# 4_RK3399_EMMC_ADC_PCIE.net
KiCad netlist of a schematic drawn in Altium Designer
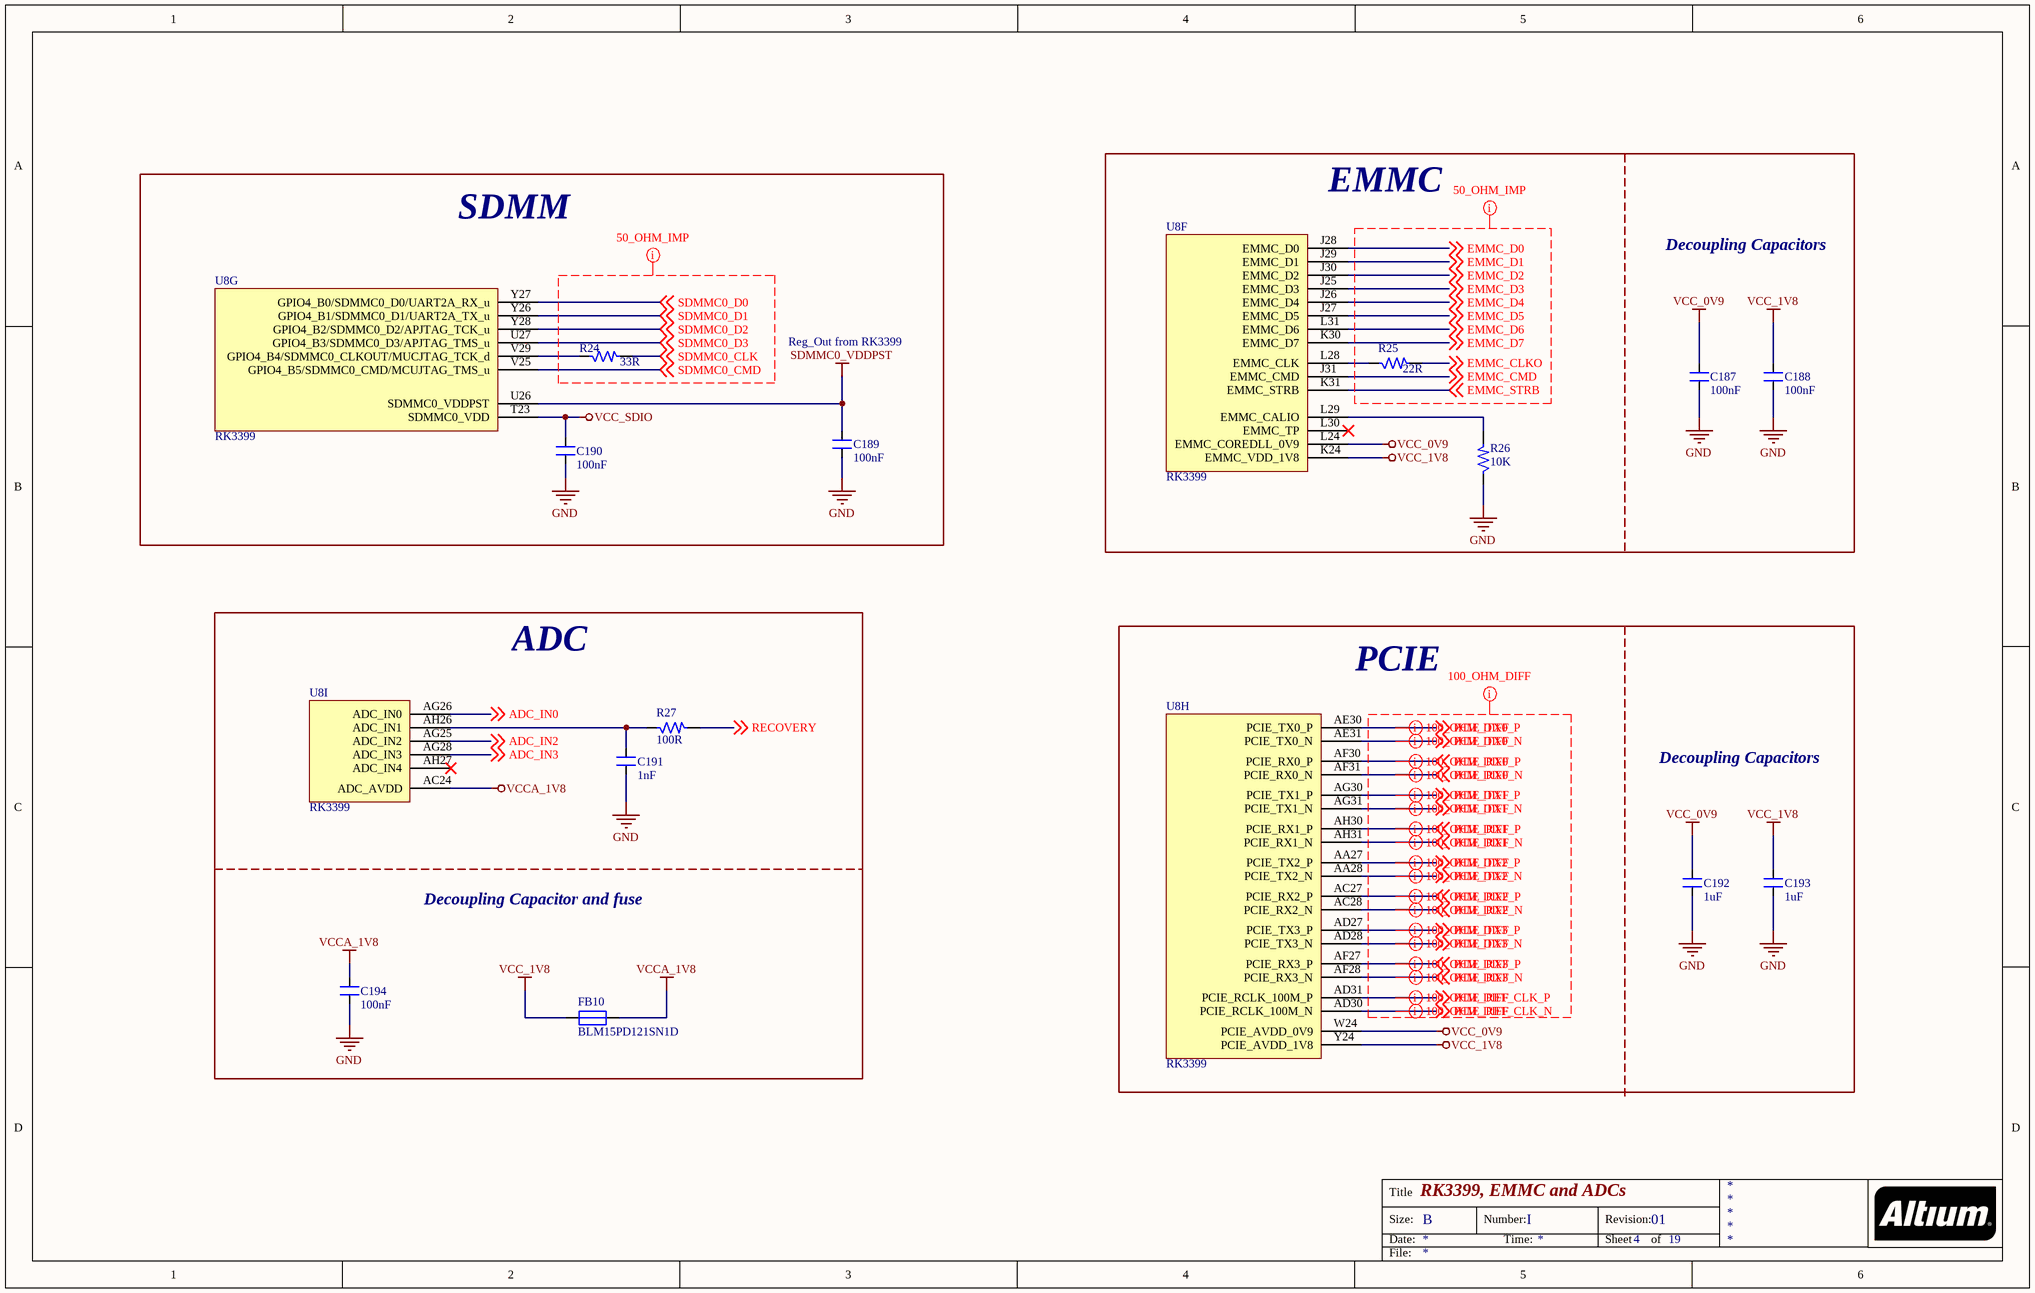
[diagram p0: [4] RK3399_EMMC_ADC_PCIE.SchDoc]

(export (version "E")
  (design (tool "Eeschema 10.0.6"))
  (components
    (comp (ref "C187")
      (value "100nF")
      (footprint "CAP_0201")
      (description "0.1µF ±10% 25V Ceramic Capacitor X5R 0201 (0603 Metric)")
      (fields
        (field (name "MANUFACTURER") "TDK Corporation")
        (field (name "MANUFACTURER PART NUMBER") "C0603X5R1E104K030BB")
      )
      (libsource (lib "EsteemPCB_SOM_Course_intlib") (part "CAP_100nF-25V-10%-0201"))
    )
    (comp (ref "C188")
      (value "100nF")
      (footprint "CAP_0201")
      (description "0.1µF ±10% 25V Ceramic Capacitor X5R 0201 (0603 Metric)")
      (fields
        (field (name "MANUFACTURER") "TDK Corporation")
        (field (name "MANUFACTURER PART NUMBER") "C0603X5R1E104K030BB")
      )
      (libsource (lib "EsteemPCB_SOM_Course_intlib") (part "CAP_100nF-25V-10%-0201"))
    )
    (comp (ref "C189")
      (value "100nF")
      (footprint "CAP_0201")
      (description "0.1µF ±10% 25V Ceramic Capacitor X5R 0201 (0603 Metric)")
      (fields
        (field (name "MANUFACTURER") "TDK Corporation")
        (field (name "MANUFACTURER PART NUMBER") "C0603X5R1E104K030BB")
      )
      (libsource (lib "EsteemPCB_SOM_Course_intlib") (part "CAP_100nF-25V-10%-0201"))
    )
    (comp (ref "C190")
      (value "100nF")
      (footprint "CAP_0201")
      (description "0.1µF ±10% 25V Ceramic Capacitor X5R 0201 (0603 Metric)")
      (fields
        (field (name "MANUFACTURER") "TDK Corporation")
        (field (name "MANUFACTURER PART NUMBER") "C0603X5R1E104K030BB")
      )
      (libsource (lib "EsteemPCB_SOM_Course_intlib") (part "CAP_100nF-25V-10%-0201"))
    )
    (comp (ref "C191")
      (value "1nF")
      (footprint "CAP_0201")
      (description "1000pF ±10% 16V Ceramic Capacitor X7R 0201 (0603 Metric)")
      (fields
        (field (name "MANUFACTURER") "Murata Electronics")
        (field (name "MANUFACTURER PART NUMBER") "GRM033R71C102KA01D")
      )
      (libsource (lib "EsteemPCB_SOM_Course_intlib") (part "CAP_1nF-16V-10%-0201"))
    )
    (comp (ref "C192")
      (value "1uF")
      (footprint "CAP_0201")
      (description "1µF ±20% 16V Ceramic Capacitor X5R 0201 (0603 Metric)")
      (fields
        (field (name "MANUFACTURER") "Samsung Electro-Mechanics")
        (field (name "MANUFACTURER PART NUMBER") "CL03A105MO3NRNH")
      )
      (libsource (lib "EsteemPCB_SOM_Course_intlib") (part "CAP_1uF-16V-10%-0201"))
    )
    (comp (ref "C193")
      (value "1uF")
      (footprint "CAP_0201")
      (description "1µF ±20% 16V Ceramic Capacitor X5R 0201 (0603 Metric)")
      (fields
        (field (name "MANUFACTURER") "Samsung Electro-Mechanics")
        (field (name "MANUFACTURER PART NUMBER") "CL03A105MO3NRNH")
      )
      (libsource (lib "EsteemPCB_SOM_Course_intlib") (part "CAP_1uF-16V-10%-0201"))
    )
    (comp (ref "C194")
      (value "100nF")
      (footprint "CAP_0201")
      (description "0.1µF ±10% 25V Ceramic Capacitor X5R 0201 (0603 Metric)")
      (fields
        (field (name "MANUFACTURER") "TDK Corporation")
        (field (name "MANUFACTURER PART NUMBER") "C0603X5R1E104K030BB")
      )
      (libsource (lib "EsteemPCB_SOM_Course_intlib") (part "CAP_100nF-25V-10%-0201"))
    )
    (comp (ref "FB10")
      (value "BLM15PD121SN1D")
      (footprint "RES_0402")
      (description "120 Ohms @ 100MHz 1 Power Line Ferrite Bead 0402 (1005 Metric) 1.3A 90mOhm")
      (fields (field (name "MANUFACTURER") "Murata Electronics"))
      (libsource (lib "EsteemPCB_SOM_Course_intlib") (part "FB_120R-1.3A-100Mhz-0402"))
    )
    (comp (ref "R24")
      (value "33R")
      (footprint "RES_0201")
      (description "33 Ohms ±1% 0.05W, 1/20W Chip Resistor 0201 (0603 Metric) Thick Film")
      (fields
        (field (name "MANUFACTURER") "Yageo")
        (field (name "MANUFACTURER PART NUMBER") "RC0201FR-0733RL")
      )
      (libsource (lib "EsteemPCB_SOM_Course_intlib") (part "RES_33R-0.05W-1%-0201"))
    )
    (comp (ref "R25")
      (value "22R")
      (footprint "RES_0201")
      (description "22 Ohms ±1% 0.05W, 1/20W Chip Resistor 0201 (0603 Metric) Moisture Resistant Thick Film")
      (fields
        (field (name "MANUFACTURER") "Yageo")
        (field (name "MANUFACTURER PART NUMBER") "RC0201FR-0722RL")
      )
      (libsource (lib "EsteemPCB_SOM_Course_intlib") (part "RES_22R-0.05W-1%-0201"))
    )
    (comp (ref "R26")
      (value "10K")
      (footprint "RES_0201")
      (description "10 kOhms ±1% 0.05W, 1/20W Chip Resistor 0201 (0603 Metric) Thick Film")
      (fields
        (field (name "MANUFACTURER") "Stackpole Electronics Inc")
        (field (name "MANUFACTURER PART NUMBER") "RMCF0201FT10K0")
      )
      (libsource (lib "EsteemPCB_SOM_Course_intlib") (part "RES_10K-0.05W-1%-0201"))
    )
    (comp (ref "R27")
      (value "100R")
      (footprint "RES_0201")
      (description "100 kOhms ±1% 0.05W, 1/20W Chip Resistor 0201 (0603 Metric) Automotive AEC-Q200 Thick Film")
      (fields
        (field (name "MANUFACTURER") "Panasonic Electronic Components")
        (field (name "MANUFACTURER PART NUMBER") "ERJ-1GNF1003C")
      )
      (libsource (lib "EsteemPCB_SOM_Course_intlib") (part "RES_100R-0.05W-1%-0201"))
    )
    (comp (ref "U8")
      (value "RK3399")
      (footprint "FBGA828_23_826X826")
      (description "RK3399 is a low power, high performance processor for computing, personal mobile.")
      (fields (field (name "MANUFACTURER") "Rockchip"))
      (libsource (lib "EsteemPCB_SOM_Course_intlib") (part "IC_RK3399-FCBGA828"))
    )
  )
  (nets
    (net (code "1") (name "ADC_IN0") (class "Default")
      (node (ref "U8") (pin "AG26") (pinfunction "ADC_IN0_AG26") (pintype "passive"))
    )
    (net (code "2") (name "ADC_IN2") (class "Default")
      (node (ref "U8") (pin "AG25") (pinfunction "ADC_IN2_AG25") (pintype "passive"))
    )
    (net (code "3") (name "ADC_IN3") (class "Default")
      (node (ref "U8") (pin "AG28") (pinfunction "ADC_IN3_AG28") (pintype "passive"))
    )
    (net (code "4") (name "EMMC_CLKO") (class "Default")
      (node (ref "R25") (pin "2") (pinfunction "2_2") (pintype "passive"))
    )
    (net (code "5") (name "EMMC_CMD") (class "Default")
      (node (ref "U8") (pin "J31") (pinfunction "EMMC_CMD_J31") (pintype "passive"))
    )
    (net (code "6") (name "EMMC_D0") (class "Default")
      (node (ref "U8") (pin "J28") (pinfunction "EMMC_D0_J28") (pintype "passive"))
    )
    (net (code "7") (name "EMMC_D1") (class "Default")
      (node (ref "U8") (pin "J29") (pinfunction "EMMC_D1_J29") (pintype "passive"))
    )
    (net (code "8") (name "EMMC_D2") (class "Default")
      (node (ref "U8") (pin "J30") (pinfunction "EMMC_D2_J30") (pintype "passive"))
    )
    (net (code "9") (name "EMMC_D3") (class "Default")
      (node (ref "U8") (pin "J25") (pinfunction "EMMC_D3_J25") (pintype "passive"))
    )
    (net (code "10") (name "EMMC_D4") (class "Default")
      (node (ref "U8") (pin "J26") (pinfunction "EMMC_D4_J26") (pintype "passive"))
    )
    (net (code "11") (name "EMMC_D5") (class "Default")
      (node (ref "U8") (pin "J27") (pinfunction "EMMC_D5_J27") (pintype "passive"))
    )
    (net (code "12") (name "EMMC_D6") (class "Default")
      (node (ref "U8") (pin "L31") (pinfunction "EMMC_D6_L31") (pintype "passive"))
    )
    (net (code "13") (name "EMMC_D7") (class "Default")
      (node (ref "U8") (pin "K30") (pinfunction "EMMC_D7_K30") (pintype "passive"))
    )
    (net (code "14") (name "EMMC_STRB") (class "Default")
      (node (ref "U8") (pin "K31") (pinfunction "EMMC_STRB_K31") (pintype "passive"))
    )
    (net (code "15") (name "GND") (class "Default")
      (node (ref "C187") (pin "1") (pinfunction "1_1") (pintype "passive"))
      (node (ref "C188") (pin "1") (pinfunction "1_1") (pintype "passive"))
      (node (ref "C189") (pin "1") (pinfunction "1_1") (pintype "passive"))
      (node (ref "C190") (pin "1") (pinfunction "1_1") (pintype "passive"))
      (node (ref "C191") (pin "1") (pinfunction "1_1") (pintype "passive"))
      (node (ref "C192") (pin "1") (pinfunction "1_1") (pintype "passive"))
      (node (ref "C193") (pin "1") (pinfunction "1_1") (pintype "passive"))
      (node (ref "C194") (pin "1") (pinfunction "1_1") (pintype "passive"))
      (node (ref "R26") (pin "1") (pinfunction "1_1") (pintype "passive"))
    )
    (net (code "16") (name "Net-(U8F-EMMC_CALIO)") (class "Default")
      (node (ref "R26") (pin "2") (pinfunction "2_2") (pintype "passive"))
      (node (ref "U8") (pin "L29") (pinfunction "EMMC_CALIO_L29") (pintype "passive"))
    )
    (net (code "17") (name "Net-(U8F-EMMC_CLK)") (class "Default")
      (node (ref "R25") (pin "1") (pinfunction "1_1") (pintype "passive"))
      (node (ref "U8") (pin "L28") (pinfunction "EMMC_CLK_L28") (pintype "passive"))
    )
    (net (code "18") (name "Net-(U8G-GPIO4_B4{slash}SDMMC0_CLKOUT{slash}MUCJTAG_TCK_d)") (class "Default")
      (node (ref "R24") (pin "1") (pinfunction "1_1") (pintype "passive"))
      (node (ref "U8") (pin "V29") (pinfunction "GPIO4_B4/SDMMC0_CLKOUT/MUCJTAG_TCK_d_V29") (pintype "passive"))
    )
    (net (code "19") (name "Net-(U8I-ADC_IN1)") (class "Default")
      (node (ref "C191") (pin "2") (pinfunction "2_2") (pintype "passive"))
      (node (ref "R27") (pin "1") (pinfunction "1_1") (pintype "passive"))
      (node (ref "U8") (pin "AH26") (pinfunction "ADC_IN1_AH26") (pintype "passive"))
    )
    (net (code "20") (name "PCIE_REF_CLK_N") (class "Default")
      (node (ref "U8") (pin "AD30") (pinfunction "PCIE_RCLK_100M_N_AD30") (pintype "passive"))
    )
    (net (code "21") (name "PCIE_REF_CLK_P") (class "Default")
      (node (ref "U8") (pin "AD31") (pinfunction "PCIE_RCLK_100M_P_AD31") (pintype "passive"))
    )
    (net (code "22") (name "PCIE_RX0_N") (class "Default")
      (node (ref "U8") (pin "AF31") (pinfunction "PCIE_RX0_N_AF31") (pintype "passive"))
    )
    (net (code "23") (name "PCIE_RX0_P") (class "Default")
      (node (ref "U8") (pin "AF30") (pinfunction "PCIE_RX0_P_AF30") (pintype "passive"))
    )
    (net (code "24") (name "PCIE_RX1_N") (class "Default")
      (node (ref "U8") (pin "AH31") (pinfunction "PCIE_RX1_N_AH31") (pintype "passive"))
    )
    (net (code "25") (name "PCIE_RX1_P") (class "Default")
      (node (ref "U8") (pin "AH30") (pinfunction "PCIE_RX1_P_AH30") (pintype "passive"))
    )
    (net (code "26") (name "PCIE_RX2_N") (class "Default")
      (node (ref "U8") (pin "AC28") (pinfunction "PCIE_RX2_N_AC28") (pintype "passive"))
    )
    (net (code "27") (name "PCIE_RX2_P") (class "Default")
      (node (ref "U8") (pin "AC27") (pinfunction "PCIE_RX2_P_AC27") (pintype "passive"))
    )
    (net (code "28") (name "PCIE_RX3_N") (class "Default")
      (node (ref "U8") (pin "AF28") (pinfunction "PCIE_RX3_N_AF28") (pintype "passive"))
    )
    (net (code "29") (name "PCIE_RX3_P") (class "Default")
      (node (ref "U8") (pin "AF27") (pinfunction "PCIE_RX3_P_AF27") (pintype "passive"))
    )
    (net (code "30") (name "PCIE_TX0_N") (class "Default")
      (node (ref "U8") (pin "AE31") (pinfunction "PCIE_TX0_N_AE31") (pintype "passive"))
    )
    (net (code "31") (name "PCIE_TX0_P") (class "Default")
      (node (ref "U8") (pin "AE30") (pinfunction "PCIE_TX0_P_AE30") (pintype "passive"))
    )
    (net (code "32") (name "PCIE_TX1_N") (class "Default")
      (node (ref "U8") (pin "AG31") (pinfunction "PCIE_TX1_N_AG31") (pintype "passive"))
    )
    (net (code "33") (name "PCIE_TX1_P") (class "Default")
      (node (ref "U8") (pin "AG30") (pinfunction "PCIE_TX1_P_AG30") (pintype "passive"))
    )
    (net (code "34") (name "PCIE_TX2_N") (class "Default")
      (node (ref "U8") (pin "AA28") (pinfunction "PCIE_TX2_N_AA28") (pintype "passive"))
    )
    (net (code "35") (name "PCIE_TX2_P") (class "Default")
      (node (ref "U8") (pin "AA27") (pinfunction "PCIE_TX2_P_AA27") (pintype "passive"))
    )
    (net (code "36") (name "PCIE_TX3_N") (class "Default")
      (node (ref "U8") (pin "AD28") (pinfunction "PCIE_TX3_N_AD28") (pintype "passive"))
    )
    (net (code "37") (name "PCIE_TX3_P") (class "Default")
      (node (ref "U8") (pin "AD27") (pinfunction "PCIE_TX3_P_AD27") (pintype "passive"))
    )
    (net (code "38") (name "RECOVERY") (class "Default")
      (node (ref "R27") (pin "2") (pinfunction "2_2") (pintype "passive"))
    )
    (net (code "39") (name "SDMMC0_CLK") (class "Default")
      (node (ref "R24") (pin "2") (pinfunction "2_2") (pintype "passive"))
    )
    (net (code "40") (name "SDMMC0_CMD") (class "Default")
      (node (ref "U8") (pin "V25") (pinfunction "GPIO4_B5/SDMMC0_CMD/MCUJTAG_TMS_u_V25") (pintype "passive"))
    )
    (net (code "41") (name "SDMMC0_D0") (class "Default")
      (node (ref "U8") (pin "Y27") (pinfunction "GPIO4_B0/SDMMC0_D0/UART2A_RX_u_Y27") (pintype "passive"))
    )
    (net (code "42") (name "SDMMC0_D1") (class "Default")
      (node (ref "U8") (pin "Y26") (pinfunction "GPIO4_B1/SDMMC0_D1/UART2A_TX_u_Y26") (pintype "passive"))
    )
    (net (code "43") (name "SDMMC0_D2") (class "Default")
      (node (ref "U8") (pin "Y28") (pinfunction "GPIO4_B2/SDMMC0_D2/APJTAG_TCK_u_Y28") (pintype "passive"))
    )
    (net (code "44") (name "SDMMC0_D3") (class "Default")
      (node (ref "U8") (pin "U27") (pinfunction "GPIO4_B3/SDMMC0_D3/APJTAG_TMS_u_U27") (pintype "passive"))
    )
    (net (code "45") (name "SDMMC0_VDDPST") (class "Default")
      (node (ref "C189") (pin "2") (pinfunction "2_2") (pintype "passive"))
      (node (ref "U8") (pin "U26") (pinfunction "SDMMC0_VDDPST_U26") (pintype "passive"))
    )
    (net (code "46") (name "VCCA_1V8") (class "Default")
      (node (ref "C194") (pin "2") (pinfunction "2_2") (pintype "passive"))
      (node (ref "FB10") (pin "2") (pinfunction "2_2") (pintype "passive"))
      (node (ref "U8") (pin "AC24") (pinfunction "ADC_AVDD_AC24") (pintype "passive"))
    )
    (net (code "47") (name "VCC_0V9") (class "Default")
      (node (ref "C187") (pin "2") (pinfunction "2_2") (pintype "passive"))
      (node (ref "C192") (pin "2") (pinfunction "2_2") (pintype "passive"))
      (node (ref "U8") (pin "L24") (pinfunction "EMMC_COREDLL_0V9_L24") (pintype "passive"))
      (node (ref "U8") (pin "W24") (pinfunction "PCIE_AVDD_0V9_W24") (pintype "passive"))
    )
    (net (code "48") (name "VCC_1V8") (class "Default")
      (node (ref "C188") (pin "2") (pinfunction "2_2") (pintype "passive"))
      (node (ref "C193") (pin "2") (pinfunction "2_2") (pintype "passive"))
      (node (ref "FB10") (pin "1") (pinfunction "1_1") (pintype "passive"))
      (node (ref "U8") (pin "K24") (pinfunction "EMMC_VDD_1V8_K24") (pintype "passive"))
      (node (ref "U8") (pin "Y24") (pinfunction "PCIE_AVDD_1V8_Y24") (pintype "passive"))
    )
    (net (code "49") (name "VCC_SDIO") (class "Default")
      (node (ref "C190") (pin "2") (pinfunction "2_2") (pintype "passive"))
      (node (ref "U8") (pin "T23") (pinfunction "SDMMC0_VDD_T23") (pintype "passive"))
    )
    (net (code "50") (name "unconnected-(U8F-EMMC_TP-PadL30)") (class "Default")
      (node (ref "U8") (pin "L30") (pinfunction "EMMC_TP_L30") (pintype "passive+no_connect"))
    )
    (net (code "51") (name "unconnected-(U8I-ADC_IN4-PadAH27)") (class "Default")
      (node (ref "U8") (pin "AH27") (pinfunction "ADC_IN4_AH27") (pintype "passive+no_connect"))
    )
  )
)
